# LS1-LS2_audio.net
KiCad netlist of a schematic drawn in Altium Designer
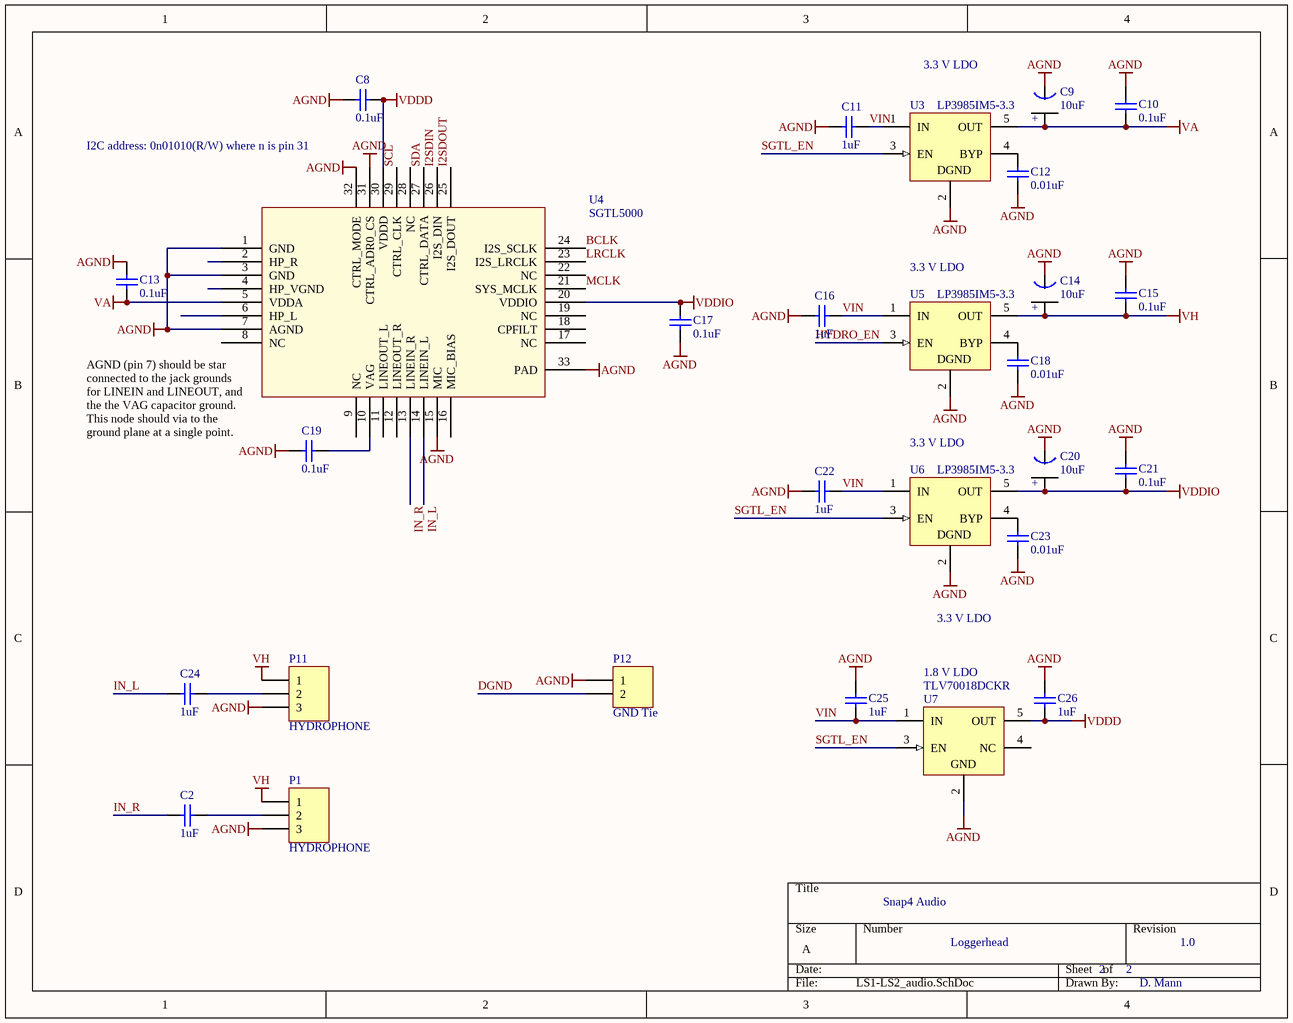
[diagram p0: LS1-LS2_audio.SchDoc]

(export (version "E")
  (design (tool "Eeschema 10.0.6"))
  (components
    (comp (ref "C2")
      (value "1uF")
      (footprint "0402")
      (description "Ceramic Chip Capacitor - Standard")
      (fields (field (name "PUBLISHER") "Altium Limited"))
      (libsource (lib "KEMET Chip Capacitor") (part "C0402"))
    )
    (comp (ref "C8")
      (value "0.1uF")
      (footprint "0402")
      (description "Ceramic Chip Capacitor - Standard")
      (fields (field (name "PUBLISHER") "Altium Limited"))
      (libsource (lib "KEMET Chip Capacitor") (part "C0402"))
    )
    (comp (ref "C9") (value "10uF") (footprint "Tant0805") (libsource (lib "Loggerhead") (part "Tant0805")))
    (comp (ref "C10")
      (value "0.1uF")
      (footprint "0402")
      (description "Ceramic Chip Capacitor - Standard")
      (fields (field (name "PUBLISHER") "Altium Limited"))
      (libsource (lib "KEMET Chip Capacitor") (part "C0402"))
    )
    (comp (ref "C11")
      (value "1uF")
      (footprint "0402")
      (description "Ceramic Chip Capacitor - Standard")
      (fields (field (name "PUBLISHER") "Altium Limited"))
      (libsource (lib "KEMET Chip Capacitor") (part "C0402"))
    )
    (comp (ref "C12")
      (value "0.01uF")
      (footprint "0402")
      (description "Ceramic Chip Capacitor - Standard")
      (fields (field (name "PUBLISHER") "Altium Limited"))
      (libsource (lib "KEMET Chip Capacitor") (part "C0402"))
    )
    (comp (ref "C13")
      (value "0.1uF")
      (footprint "0402")
      (description "Ceramic Chip Capacitor - Standard")
      (fields (field (name "PUBLISHER") "Altium Limited"))
      (libsource (lib "KEMET Chip Capacitor") (part "C0402"))
    )
    (comp (ref "C14") (value "10uF") (footprint "Tant0805") (libsource (lib "Loggerhead") (part "Tant0805")))
    (comp (ref "C15")
      (value "0.1uF")
      (footprint "0402")
      (description "Ceramic Chip Capacitor - Standard")
      (fields (field (name "PUBLISHER") "Altium Limited"))
      (libsource (lib "KEMET Chip Capacitor") (part "C0402"))
    )
    (comp (ref "C16")
      (value "1uF")
      (footprint "0402")
      (description "Ceramic Chip Capacitor - Standard")
      (fields (field (name "PUBLISHER") "Altium Limited"))
      (libsource (lib "KEMET Chip Capacitor") (part "C0402"))
    )
    (comp (ref "C17")
      (value "0.1uF")
      (footprint "0402")
      (description "Ceramic Chip Capacitor - Standard")
      (fields (field (name "PUBLISHER") "Altium Limited"))
      (libsource (lib "KEMET Chip Capacitor") (part "C0402"))
    )
    (comp (ref "C18")
      (value "0.01uF")
      (footprint "0402")
      (description "Ceramic Chip Capacitor - Standard")
      (fields (field (name "PUBLISHER") "Altium Limited"))
      (libsource (lib "KEMET Chip Capacitor") (part "C0402"))
    )
    (comp (ref "C19")
      (value "0.1uF")
      (footprint "0402")
      (description "Ceramic Chip Capacitor - Standard")
      (fields (field (name "PUBLISHER") "Altium Limited"))
      (libsource (lib "KEMET Chip Capacitor") (part "C0402"))
    )
    (comp (ref "C20") (value "10uF") (footprint "Tant0805") (libsource (lib "Loggerhead") (part "Tant0805")))
    (comp (ref "C21")
      (value "0.1uF")
      (footprint "0402")
      (description "Ceramic Chip Capacitor - Standard")
      (fields (field (name "PUBLISHER") "Altium Limited"))
      (libsource (lib "KEMET Chip Capacitor") (part "C0402"))
    )
    (comp (ref "C22")
      (value "1uF")
      (footprint "0402")
      (description "Ceramic Chip Capacitor - Standard")
      (fields (field (name "PUBLISHER") "Altium Limited"))
      (libsource (lib "KEMET Chip Capacitor") (part "C0402"))
    )
    (comp (ref "C23")
      (value "0.01uF")
      (footprint "0402")
      (description "Ceramic Chip Capacitor - Standard")
      (fields (field (name "PUBLISHER") "Altium Limited"))
      (libsource (lib "KEMET Chip Capacitor") (part "C0402"))
    )
    (comp (ref "C24")
      (value "1uF")
      (footprint "0402")
      (description "Ceramic Chip Capacitor - Standard")
      (fields (field (name "PUBLISHER") "Altium Limited"))
      (libsource (lib "KEMET Chip Capacitor") (part "C0402"))
    )
    (comp (ref "C25")
      (value "1uF")
      (footprint "0402")
      (description "Ceramic Chip Capacitor - Standard")
      (fields (field (name "PUBLISHER") "Altium Limited"))
      (libsource (lib "KEMET Chip Capacitor") (part "C0402"))
    )
    (comp (ref "C26")
      (value "1uF")
      (footprint "0402")
      (description "Ceramic Chip Capacitor - Standard")
      (fields (field (name "PUBLISHER") "Altium Limited"))
      (libsource (lib "KEMET Chip Capacitor") (part "C0402"))
    )
    (comp (ref "P1")
      (value "HYDROPHONE")
      (footprint "HDR1X3")
      (description "Header, 3-Pin")
      (fields (field (name "PUBLISHER") "Altium Limited"))
      (libsource (lib "Miscellaneous Connectors") (part "Header 3"))
    )
    (comp (ref "P11")
      (value "HYDROPHONE")
      (footprint "HDR1X3")
      (description "Header, 3-Pin")
      (fields (field (name "PUBLISHER") "Altium Limited"))
      (libsource (lib "Miscellaneous Connectors") (part "Header 3"))
    )
    (comp (ref "P12")
      (value "GND Tie")
      (footprint "HDR1X2")
      (description "Header, 2-Pin")
      (fields (field (name "PUBLISHER") "Altium Limited"))
      (libsource (lib "Miscellaneous Connectors") (part "Header 2"))
    )
    (comp (ref "U3")
      (value "LP3985IM5-3.3")
      (footprint "MF05A_N")
      (description "Micropower, 150mA Low-Noise Ultra Low-Dropout CMOS Voltage Regulator")
      (fields
        (field (name "MANUFACTURER") "National Semiconductor")
        (field (name "DIGIKEYPARTNUMBER") "LP3985IM5-3.3CT-ND")
        (field (name "PUBLISHER") "Altium Limited")
      )
      (libsource (lib "NSC LDO") (part "LP3985IM5-3.3"))
    )
    (comp (ref "U4") (value "SGTL5000") (footprint "QFN32") (libsource (lib "Loggerhead") (part "SGTL5000")))
    (comp (ref "U5")
      (value "LP3985IM5-3.3")
      (footprint "MF05A_N")
      (description "Micropower, 150mA Low-Noise Ultra Low-Dropout CMOS Voltage Regulator")
      (fields
        (field (name "MANUFACTURER") "National Semiconductor")
        (field (name "DIGIKEYPARTNUMBER") "LP3985IM5-3.3CT-ND")
        (field (name "PUBLISHER") "Altium Limited")
      )
      (libsource (lib "NSC LDO") (part "LP3985IM5-3.3"))
    )
    (comp (ref "U6")
      (value "LP3985IM5-3.3")
      (footprint "MF05A_N")
      (description "Micropower, 150mA Low-Noise Ultra Low-Dropout CMOS Voltage Regulator")
      (fields
        (field (name "MANUFACTURER") "National Semiconductor")
        (field (name "DIGIKEYPARTNUMBER") "LP3985IM5-3.3CT-ND")
        (field (name "PUBLISHER") "Altium Limited")
      )
      (libsource (lib "NSC LDO") (part "LP3985IM5-3.3"))
    )
    (comp (ref "U7")
      (value "TLV70018DCKR")
      (footprint "TI-DCK5_V")
      (fields (field (name "MANUFACTURER") "Texas Instruments"))
      (libsource (lib "TI Power Management Linear Regulator Single Channel LDO (0-350mA)") (part "TLV70018DCKR"))
    )
  )
  (nets
    (net (code "1") (name "/BCLK") (class "Default")
      (node (ref "U4") (pin "24") (pinfunction "I2S_SCLK_24") (pintype "passive"))
    )
    (net (code "2") (name "/DGND") (class "Default")
      (node (ref "P12") (pin "2") (pinfunction "2_2") (pintype "passive"))
    )
    (net (code "3") (name "/HYDRO_EN") (class "Default")
      (node (ref "U5") (pin "3") (pinfunction "EN_3") (pintype "input"))
    )
    (net (code "4") (name "/I2SDIN") (class "Default")
      (node (ref "U4") (pin "26") (pinfunction "I2S_DIN_26") (pintype "passive"))
    )
    (net (code "5") (name "/I2SDOUT") (class "Default")
      (node (ref "U4") (pin "25") (pinfunction "I2S_DOUT_25") (pintype "passive"))
    )
    (net (code "6") (name "/IN_L") (class "Default")
      (node (ref "C24") (pin "2") (pinfunction "2_2") (pintype "passive"))
      (node (ref "U4") (pin "14") (pinfunction "LINEIN_L_14") (pintype "passive"))
    )
    (net (code "7") (name "/IN_R") (class "Default")
      (node (ref "C2") (pin "2") (pinfunction "2_2") (pintype "passive"))
      (node (ref "U4") (pin "13") (pinfunction "LINEIN_R_13") (pintype "passive"))
    )
    (net (code "8") (name "/LRCLK") (class "Default")
      (node (ref "U4") (pin "23") (pinfunction "I2S_LRCLK_23") (pintype "passive"))
    )
    (net (code "9") (name "/MCLK") (class "Default")
      (node (ref "U4") (pin "21") (pinfunction "SYS_MCLK_21") (pintype "passive"))
    )
    (net (code "10") (name "/SCL") (class "Default")
      (node (ref "U4") (pin "29") (pinfunction "CTRL_CLK_29") (pintype "passive"))
    )
    (net (code "11") (name "/SDA") (class "Default")
      (node (ref "U4") (pin "27") (pinfunction "CTRL_DATA_27") (pintype "passive"))
    )
    (net (code "12") (name "/SGTL_EN") (class "Default")
      (node (ref "U3") (pin "3") (pinfunction "EN_3") (pintype "input"))
      (node (ref "U6") (pin "3") (pinfunction "EN_3") (pintype "input"))
      (node (ref "U7") (pin "3") (pinfunction "EN_3") (pintype "input"))
    )
    (net (code "13") (name "/VIN") (class "Default")
      (node (ref "C11") (pin "1") (pinfunction "1_1") (pintype "passive"))
      (node (ref "C16") (pin "1") (pinfunction "1_1") (pintype "passive"))
      (node (ref "C22") (pin "1") (pinfunction "1_1") (pintype "passive"))
      (node (ref "C25") (pin "1") (pinfunction "1_1") (pintype "passive"))
      (node (ref "U3") (pin "1") (pinfunction "IN_1") (pintype "power_in"))
      (node (ref "U5") (pin "1") (pinfunction "IN_1") (pintype "power_in"))
      (node (ref "U6") (pin "1") (pinfunction "IN_1") (pintype "power_in"))
      (node (ref "U7") (pin "1") (pinfunction "IN_1") (pintype "power_in"))
    )
    (net (code "14") (name "AGND") (class "Default")
      (node (ref "C10") (pin "2") (pinfunction "2_2") (pintype "passive"))
      (node (ref "C11") (pin "2") (pinfunction "2_2") (pintype "passive"))
      (node (ref "C12") (pin "2") (pinfunction "2_2") (pintype "passive"))
      (node (ref "C13") (pin "2") (pinfunction "2_2") (pintype "passive"))
      (node (ref "C14") (pin "1") (pinfunction "GND_1") (pintype "passive"))
      (node (ref "C15") (pin "2") (pinfunction "2_2") (pintype "passive"))
      (node (ref "C16") (pin "2") (pinfunction "2_2") (pintype "passive"))
      (node (ref "C17") (pin "2") (pinfunction "2_2") (pintype "passive"))
      (node (ref "C18") (pin "2") (pinfunction "2_2") (pintype "passive"))
      (node (ref "C19") (pin "2") (pinfunction "2_2") (pintype "passive"))
      (node (ref "C20") (pin "1") (pinfunction "GND_1") (pintype "passive"))
      (node (ref "C21") (pin "2") (pinfunction "2_2") (pintype "passive"))
      (node (ref "C22") (pin "2") (pinfunction "2_2") (pintype "passive"))
      (node (ref "C23") (pin "2") (pinfunction "2_2") (pintype "passive"))
      (node (ref "C25") (pin "2") (pinfunction "2_2") (pintype "passive"))
      (node (ref "C26") (pin "2") (pinfunction "2_2") (pintype "passive"))
      (node (ref "C8") (pin "2") (pinfunction "2_2") (pintype "passive"))
      (node (ref "C9") (pin "1") (pinfunction "GND_1") (pintype "passive"))
      (node (ref "P1") (pin "3") (pinfunction "3_3") (pintype "passive"))
      (node (ref "P11") (pin "3") (pinfunction "3_3") (pintype "passive"))
      (node (ref "P12") (pin "1") (pinfunction "1_1") (pintype "passive"))
      (node (ref "U3") (pin "2") (pinfunction "GND_2") (pintype "power_in"))
      (node (ref "U4") (pin "1") (pinfunction "GND_1") (pintype "passive"))
      (node (ref "U4") (pin "15") (pinfunction "MIC_15") (pintype "passive"))
      (node (ref "U4") (pin "3") (pinfunction "GND_3") (pintype "passive"))
      (node (ref "U4") (pin "31") (pinfunction "CTRL_ADR0_CS_31") (pintype "passive"))
      (node (ref "U4") (pin "32") (pinfunction "CTRL_MODE_32") (pintype "passive"))
      (node (ref "U4") (pin "33") (pinfunction "PAD_33") (pintype "passive"))
      (node (ref "U4") (pin "7") (pinfunction "AGND_7") (pintype "passive"))
      (node (ref "U5") (pin "2") (pinfunction "GND_2") (pintype "power_in"))
      (node (ref "U6") (pin "2") (pinfunction "GND_2") (pintype "power_in"))
      (node (ref "U7") (pin "2") (pinfunction "GND_2") (pintype "power_in"))
    )
    (net (code "15") (name "Net-(C2-Pad1)") (class "Default")
      (node (ref "C2") (pin "1") (pinfunction "1_1") (pintype "passive"))
      (node (ref "P1") (pin "2") (pinfunction "2_2") (pintype "passive"))
    )
    (net (code "16") (name "Net-(C24-Pad1)") (class "Default")
      (node (ref "C24") (pin "1") (pinfunction "1_1") (pintype "passive"))
      (node (ref "P11") (pin "2") (pinfunction "2_2") (pintype "passive"))
    )
    (net (code "17") (name "Net-(U3-BYP)") (class "Default")
      (node (ref "C12") (pin "1") (pinfunction "1_1") (pintype "passive"))
      (node (ref "U3") (pin "4") (pinfunction "BYP_4") (pintype "passive"))
    )
    (net (code "18") (name "Net-(U4-VAG)") (class "Default")
      (node (ref "C19") (pin "1") (pinfunction "1_1") (pintype "passive"))
      (node (ref "U4") (pin "10") (pinfunction "VAG_10") (pintype "passive"))
    )
    (net (code "19") (name "Net-(U5-BYP)") (class "Default")
      (node (ref "C18") (pin "1") (pinfunction "1_1") (pintype "passive"))
      (node (ref "U5") (pin "4") (pinfunction "BYP_4") (pintype "passive"))
    )
    (net (code "20") (name "Net-(U6-BYP)") (class "Default")
      (node (ref "C23") (pin "1") (pinfunction "1_1") (pintype "passive"))
      (node (ref "U6") (pin "4") (pinfunction "BYP_4") (pintype "passive"))
    )
    (net (code "21") (name "VA") (class "Default")
      (node (ref "C10") (pin "1") (pinfunction "1_1") (pintype "passive"))
      (node (ref "C13") (pin "1") (pinfunction "1_1") (pintype "passive"))
      (node (ref "C9") (pin "2") (pinfunction "+_2") (pintype "passive"))
      (node (ref "U3") (pin "5") (pinfunction "OUT_5") (pintype "power_in"))
      (node (ref "U4") (pin "5") (pinfunction "VDDA_5") (pintype "passive"))
    )
    (net (code "22") (name "VDDD") (class "Default")
      (node (ref "C26") (pin "1") (pinfunction "1_1") (pintype "passive"))
      (node (ref "C8") (pin "1") (pinfunction "1_1") (pintype "passive"))
      (node (ref "U4") (pin "30") (pinfunction "VDDD_30") (pintype "passive"))
      (node (ref "U7") (pin "5") (pinfunction "OUT_5") (pintype "power_in"))
    )
    (net (code "23") (name "VDDIO") (class "Default")
      (node (ref "C17") (pin "1") (pinfunction "1_1") (pintype "passive"))
      (node (ref "C20") (pin "2") (pinfunction "+_2") (pintype "passive"))
      (node (ref "C21") (pin "1") (pinfunction "1_1") (pintype "passive"))
      (node (ref "U4") (pin "20") (pinfunction "VDDIO_20") (pintype "passive"))
      (node (ref "U6") (pin "5") (pinfunction "OUT_5") (pintype "power_in"))
    )
    (net (code "24") (name "VH") (class "Default")
      (node (ref "C14") (pin "2") (pinfunction "+_2") (pintype "passive"))
      (node (ref "C15") (pin "1") (pinfunction "1_1") (pintype "passive"))
      (node (ref "P1") (pin "1") (pinfunction "1_1") (pintype "passive"))
      (node (ref "P11") (pin "1") (pinfunction "1_1") (pintype "passive"))
      (node (ref "U5") (pin "5") (pinfunction "OUT_5") (pintype "power_in"))
    )
    (net (code "25") (name "unconnected-(U4-CPFILT-Pad18)") (class "Default")
      (node (ref "U4") (pin "18") (pinfunction "CPFILT_18") (pintype "passive"))
    )
    (net (code "26") (name "unconnected-(U4-HP_L-Pad6)") (class "Default")
      (node (ref "U4") (pin "6") (pinfunction "HP_L_6") (pintype "passive"))
    )
    (net (code "27") (name "unconnected-(U4-HP_R-Pad2)") (class "Default")
      (node (ref "U4") (pin "2") (pinfunction "HP_R_2") (pintype "passive"))
    )
    (net (code "28") (name "unconnected-(U4-HP_VGND-Pad4)") (class "Default")
      (node (ref "U4") (pin "4") (pinfunction "HP_VGND_4") (pintype "passive"))
    )
    (net (code "29") (name "unconnected-(U4-LINEOUT_L-Pad11)") (class "Default")
      (node (ref "U4") (pin "11") (pinfunction "LINEOUT_L_11") (pintype "passive"))
    )
    (net (code "30") (name "unconnected-(U4-LINEOUT_R-Pad12)") (class "Default")
      (node (ref "U4") (pin "12") (pinfunction "LINEOUT_R_12") (pintype "passive"))
    )
    (net (code "31") (name "unconnected-(U4-MIC_BIAS-Pad16)") (class "Default")
      (node (ref "U4") (pin "16") (pinfunction "MIC_BIAS_16") (pintype "passive"))
    )
    (net (code "32") (name "unconnected-(U4-NC-Pad8)") (class "Default")
      (node (ref "U4") (pin "8") (pinfunction "NC_8") (pintype "passive"))
    )
    (net (code "33") (name "unconnected-(U4-NC-Pad9)") (class "Default")
      (node (ref "U4") (pin "9") (pinfunction "NC_9") (pintype "passive"))
    )
    (net (code "34") (name "unconnected-(U4-NC-Pad17)") (class "Default")
      (node (ref "U4") (pin "17") (pinfunction "NC_17") (pintype "passive"))
    )
    (net (code "35") (name "unconnected-(U4-NC-Pad19)") (class "Default")
      (node (ref "U4") (pin "19") (pinfunction "NC_19") (pintype "passive"))
    )
    (net (code "36") (name "unconnected-(U4-NC-Pad22)") (class "Default")
      (node (ref "U4") (pin "22") (pinfunction "NC_22") (pintype "passive"))
    )
    (net (code "37") (name "unconnected-(U4-NC-Pad28)") (class "Default")
      (node (ref "U4") (pin "28") (pinfunction "NC_28") (pintype "passive"))
    )
    (net (code "38") (name "unconnected-(U7-NC-Pad4)") (class "Default")
      (node (ref "U7") (pin "4") (pinfunction "NC_4") (pintype "passive"))
    )
  )
)
